# MB_RELAY.net
KiCad netlist of a schematic drawn in Altium Designer
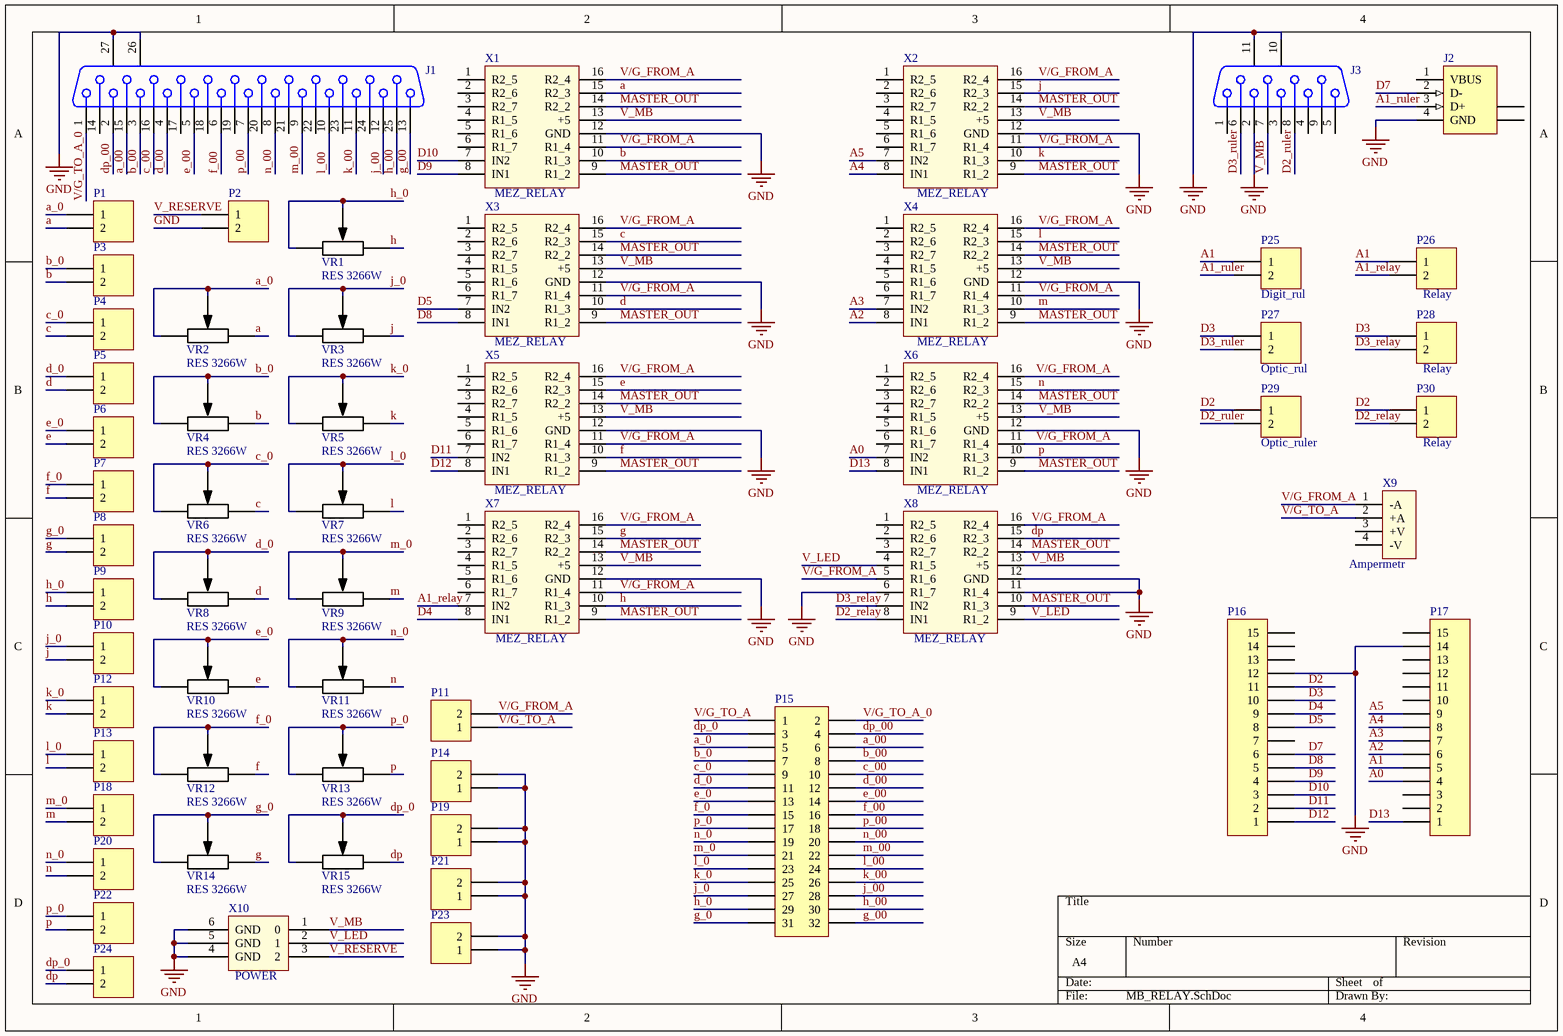
[diagram p0: MB_RELAY.SchDoc]

(export (version "E")
  (design (tool "Eeschema 10.0.6"))
  (components
    (comp (ref "J1")
      (value "D Connector 25")
      (footprint "DSUB1.385-2H25A")
      (description "Receptacle Assembly, 25 Position, Right Angle")
      (fields (field (name "PUBLISHER") "Altium Limited"))
      (libsource (lib "Miscellaneous Connectors") (part "D Connector 25"))
    )
    (comp (ref "J2")
      (value "1-353576-1")
      (footprint "353576")
      (description "USB 1.1, Right Angle, SMT, A Type, Receptacle, 4 Position, White")
      (fields (field (name "PUBLISHER") "Altium Limited"))
      (libsource (lib "AMP Serial Bus USB") (part "1-353576-1"))
    )
    (comp (ref "J3")
      (value "D Connector 9")
      (footprint "DSUB1.385-2H9")
      (description "Receptacle Assembly, 9 Position, Right Angle")
      (fields (field (name "PUBLISHER") "Altium Limited"))
      (libsource (lib "Miscellaneous Connectors") (part "D Connector 9"))
    )
    (comp (ref "P1")
      (value "Header 2")
      (footprint "HDR1X2")
      (description "Header, 2-Pin")
      (fields (field (name "PUBLISHER") "Altium Limited"))
      (libsource (lib "") (part "Header 2_1"))
    )
    (comp (ref "P2")
      (value "Header 2")
      (footprint "HDR1X2")
      (description "Header, 2-Pin")
      (fields (field (name "PUBLISHER") "Altium Limited"))
      (libsource (lib "") (part "Header 2_1"))
    )
    (comp (ref "P3")
      (value "Header 2")
      (footprint "HDR1X2")
      (description "Header, 2-Pin")
      (fields (field (name "PUBLISHER") "Altium Limited"))
      (libsource (lib "") (part "Header 2_1"))
    )
    (comp (ref "P4")
      (value "Header 2")
      (footprint "HDR1X2")
      (description "Header, 2-Pin")
      (fields (field (name "PUBLISHER") "Altium Limited"))
      (libsource (lib "") (part "Header 2_1"))
    )
    (comp (ref "P5")
      (value "Header 2")
      (footprint "HDR1X2")
      (description "Header, 2-Pin")
      (fields (field (name "PUBLISHER") "Altium Limited"))
      (libsource (lib "") (part "Header 2_1"))
    )
    (comp (ref "P6")
      (value "GND")
      (footprint "HDR1X2")
      (description "Header, 2-Pin")
      (fields (field (name "PUBLISHER") "Altium Limited"))
      (libsource (lib "") (part "Header 2_1"))
    )
    (comp (ref "P7")
      (value "GND")
      (footprint "HDR1X2")
      (description "Header, 2-Pin")
      (fields (field (name "PUBLISHER") "Altium Limited"))
      (libsource (lib "") (part "Header 2_1"))
    )
    (comp (ref "P8")
      (value "GND")
      (footprint "HDR1X2")
      (description "Header, 2-Pin")
      (fields (field (name "PUBLISHER") "Altium Limited"))
      (libsource (lib "") (part "Header 2_1"))
    )
    (comp (ref "P9")
      (value "GND")
      (footprint "HDR1X2")
      (description "Header, 2-Pin")
      (fields (field (name "PUBLISHER") "Altium Limited"))
      (libsource (lib "") (part "Header 2_1"))
    )
    (comp (ref "P10")
      (value "Header 2")
      (footprint "HDR1X2")
      (description "Header, 2-Pin")
      (fields (field (name "PUBLISHER") "Altium Limited"))
      (libsource (lib "") (part "Header 2_1"))
    )
    (comp (ref "P11")
      (value "Header 2")
      (footprint "HDR1X2")
      (description "Header, 2-Pin")
      (fields (field (name "PUBLISHER") "Altium Limited"))
      (libsource (lib "Miscellaneous Connectors") (part "Header 2"))
    )
    (comp (ref "P12")
      (value "Header 2")
      (footprint "HDR1X2")
      (description "Header, 2-Pin")
      (fields (field (name "PUBLISHER") "Altium Limited"))
      (libsource (lib "") (part "Header 2_1"))
    )
    (comp (ref "P13")
      (value "GND")
      (footprint "HDR1X2")
      (description "Header, 2-Pin")
      (fields (field (name "PUBLISHER") "Altium Limited"))
      (libsource (lib "") (part "Header 2_1"))
    )
    (comp (ref "P14")
      (value "GND")
      (footprint "HDR1X2")
      (description "Header, 2-Pin")
      (fields (field (name "PUBLISHER") "Altium Limited"))
      (libsource (lib "Miscellaneous Connectors") (part "Header 2"))
    )
    (comp (ref "P15")
      (value "Header 16X2")
      (footprint "HDR2X16")
      (description "Header, 16-Pin, Dual row")
      (fields (field (name "PUBLISHER") "Altium Limited"))
      (libsource (lib "Miscellaneous Connectors") (part "Header 16X2"))
    )
    (comp (ref "P16")
      (value "Header 15")
      (footprint "HDR1X15")
      (description "Header, 15-Pin")
      (fields (field (name "PUBLISHER") "Altium Limited"))
      (libsource (lib "") (part "Header 15_1"))
    )
    (comp (ref "P17")
      (value "Header 15")
      (footprint "HDR1X15")
      (description "Header, 15-Pin")
      (fields (field (name "PUBLISHER") "Altium Limited"))
      (libsource (lib "Miscellaneous Connectors") (part "Header 15"))
    )
    (comp (ref "P18")
      (value "GND")
      (footprint "HDR1X2")
      (description "Header, 2-Pin")
      (fields (field (name "PUBLISHER") "Altium Limited"))
      (libsource (lib "") (part "Header 2_1"))
    )
    (comp (ref "P19")
      (value "GND")
      (footprint "HDR1X2")
      (description "Header, 2-Pin")
      (fields (field (name "PUBLISHER") "Altium Limited"))
      (libsource (lib "Miscellaneous Connectors") (part "Header 2"))
    )
    (comp (ref "P20")
      (value "GND")
      (footprint "HDR1X2")
      (description "Header, 2-Pin")
      (fields (field (name "PUBLISHER") "Altium Limited"))
      (libsource (lib "") (part "Header 2_1"))
    )
    (comp (ref "P21")
      (value "GND")
      (footprint "HDR1X2")
      (description "Header, 2-Pin")
      (fields (field (name "PUBLISHER") "Altium Limited"))
      (libsource (lib "Miscellaneous Connectors") (part "Header 2"))
    )
    (comp (ref "P22")
      (value "GND")
      (footprint "HDR1X2")
      (description "Header, 2-Pin")
      (fields (field (name "PUBLISHER") "Altium Limited"))
      (libsource (lib "") (part "Header 2_1"))
    )
    (comp (ref "P23")
      (value "GND")
      (footprint "HDR1X2")
      (description "Header, 2-Pin")
      (fields (field (name "PUBLISHER") "Altium Limited"))
      (libsource (lib "Miscellaneous Connectors") (part "Header 2"))
    )
    (comp (ref "P24")
      (value "GND")
      (footprint "HDR1X2")
      (description "Header, 2-Pin")
      (fields (field (name "PUBLISHER") "Altium Limited"))
      (libsource (lib "") (part "Header 2_1"))
    )
    (comp (ref "P25")
      (value "Digit_rul")
      (footprint "HDR1X2")
      (description "Header, 2-Pin")
      (fields (field (name "PUBLISHER") "Altium Limited"))
      (libsource (lib "") (part "Header 2_1"))
    )
    (comp (ref "P26")
      (value "Relay")
      (footprint "HDR1X2")
      (description "Header, 2-Pin")
      (fields (field (name "PUBLISHER") "Altium Limited"))
      (libsource (lib "") (part "Header 2_1"))
    )
    (comp (ref "P27")
      (value "Optic_rul")
      (footprint "HDR1X2")
      (description "Header, 2-Pin")
      (fields (field (name "PUBLISHER") "Altium Limited"))
      (libsource (lib "") (part "Header 2_1"))
    )
    (comp (ref "P28")
      (value "Relay")
      (footprint "HDR1X2")
      (description "Header, 2-Pin")
      (fields (field (name "PUBLISHER") "Altium Limited"))
      (libsource (lib "") (part "Header 2_1"))
    )
    (comp (ref "P29")
      (value "Optic_ruler")
      (footprint "HDR1X2")
      (description "Header, 2-Pin")
      (fields (field (name "PUBLISHER") "Altium Limited"))
      (libsource (lib "") (part "Header 2_1"))
    )
    (comp (ref "P30")
      (value "Relay")
      (footprint "HDR1X2")
      (description "Header, 2-Pin")
      (fields (field (name "PUBLISHER") "Altium Limited"))
      (libsource (lib "") (part "Header 2_1"))
    )
    (comp (ref "VR1")
      (value "RES 3266W")
      (footprint "aab_Passive:RES 3266W")
      (libsource (lib "aab_Schlib") (part "RES 3266W"))
    )
    (comp (ref "VR2")
      (value "RES 3266W")
      (footprint "aab_Passive:RES 3266W")
      (libsource (lib "aab_Schlib") (part "RES 3266W"))
    )
    (comp (ref "VR3")
      (value "RES 3266W")
      (footprint "aab_Passive:RES 3266W")
      (libsource (lib "aab_Schlib") (part "RES 3266W"))
    )
    (comp (ref "VR4")
      (value "RES 3266W")
      (footprint "aab_Passive:RES 3266W")
      (libsource (lib "aab_Schlib") (part "RES 3266W"))
    )
    (comp (ref "VR5")
      (value "RES 3266W")
      (footprint "aab_Passive:RES 3266W")
      (libsource (lib "aab_Schlib") (part "RES 3266W"))
    )
    (comp (ref "VR6")
      (value "RES 3266W")
      (footprint "aab_Passive:RES 3266W")
      (libsource (lib "aab_Schlib") (part "RES 3266W"))
    )
    (comp (ref "VR7")
      (value "RES 3266W")
      (footprint "aab_Passive:RES 3266W")
      (libsource (lib "aab_Schlib") (part "RES 3266W"))
    )
    (comp (ref "VR8")
      (value "RES 3266W")
      (footprint "aab_Passive:RES 3266W")
      (libsource (lib "aab_Schlib") (part "RES 3266W"))
    )
    (comp (ref "VR9")
      (value "RES 3266W")
      (footprint "aab_Passive:RES 3266W")
      (libsource (lib "aab_Schlib") (part "RES 3266W"))
    )
    (comp (ref "VR10")
      (value "RES 3266W")
      (footprint "aab_Passive:RES 3266W")
      (libsource (lib "aab_Schlib") (part "RES 3266W"))
    )
    (comp (ref "VR11")
      (value "RES 3266W")
      (footprint "aab_Passive:RES 3266W")
      (libsource (lib "aab_Schlib") (part "RES 3266W"))
    )
    (comp (ref "VR12")
      (value "RES 3266W")
      (footprint "aab_Passive:RES 3266W")
      (libsource (lib "aab_Schlib") (part "RES 3266W"))
    )
    (comp (ref "VR13")
      (value "RES 3266W")
      (footprint "aab_Passive:RES 3266W")
      (libsource (lib "aab_Schlib") (part "RES 3266W"))
    )
    (comp (ref "VR14")
      (value "RES 3266W")
      (footprint "aab_Passive:RES 3266W")
      (libsource (lib "aab_Schlib") (part "RES 3266W"))
    )
    (comp (ref "VR15")
      (value "RES 3266W")
      (footprint "aab_Passive:RES 3266W")
      (libsource (lib "aab_Schlib") (part "RES 3266W"))
    )
    (comp (ref "X1")
      (value "MEZ_RELAY")
      (footprint "MEZ_RELAY")
      (libsource (lib "msp_SchLib") (part "MEZ_RELAY"))
    )
    (comp (ref "X2")
      (value "MEZ_RELAY")
      (footprint "MEZ_RELAY")
      (libsource (lib "msp_SchLib") (part "MEZ_RELAY"))
    )
    (comp (ref "X3")
      (value "MEZ_RELAY")
      (footprint "MEZ_RELAY")
      (libsource (lib "msp_SchLib") (part "MEZ_RELAY"))
    )
    (comp (ref "X4")
      (value "MEZ_RELAY")
      (footprint "MEZ_RELAY")
      (libsource (lib "msp_SchLib") (part "MEZ_RELAY"))
    )
    (comp (ref "X5")
      (value "MEZ_RELAY")
      (footprint "MEZ_RELAY")
      (libsource (lib "msp_SchLib") (part "MEZ_RELAY"))
    )
    (comp (ref "X6")
      (value "MEZ_RELAY")
      (footprint "MEZ_RELAY")
      (libsource (lib "msp_SchLib") (part "MEZ_RELAY"))
    )
    (comp (ref "X7")
      (value "MEZ_RELAY")
      (footprint "MEZ_RELAY")
      (libsource (lib "msp_SchLib") (part "MEZ_RELAY"))
    )
    (comp (ref "X8")
      (value "MEZ_RELAY")
      (footprint "MEZ_RELAY")
      (libsource (lib "msp_SchLib") (part "MEZ_RELAY"))
    )
    (comp (ref "X9")
      (value "Ampermetr")
      (footprint "vpl_Passive:AMP_VOLTMETER")
      (libsource (lib "msp_SchLib") (part "AMP_VOLTMETR"))
    )
    (comp (ref "X10")
      (value "POWER")
      (footprint "vpl_Passive:POWER")
      (libsource (lib "msp_SchLib") (part "POWER"))
    )
  )
  (nets
    (net (code "1") (name "/A0") (class "Default")
      (node (ref "P17") (pin "4") (pinfunction "4_4") (pintype "passive"))
      (node (ref "X6") (pin "7") (pinfunction "IN2_7") (pintype "passive"))
    )
    (net (code "2") (name "/A1") (class "Default")
      (node (ref "P17") (pin "5") (pinfunction "5_5") (pintype "passive"))
      (node (ref "P25") (pin "1") (pinfunction "1_1") (pintype "passive"))
      (node (ref "P26") (pin "1") (pinfunction "1_1") (pintype "passive"))
    )
    (net (code "3") (name "/A1_relay") (class "Default")
      (node (ref "P26") (pin "2") (pinfunction "2_2") (pintype "passive"))
      (node (ref "X7") (pin "7") (pinfunction "IN2_7") (pintype "passive"))
    )
    (net (code "4") (name "/A1_ruler") (class "Default")
      (node (ref "J2") (pin "3") (pinfunction "D+_3") (pintype "input"))
      (node (ref "P25") (pin "2") (pinfunction "2_2") (pintype "passive"))
    )
    (net (code "5") (name "/A2") (class "Default")
      (node (ref "P17") (pin "6") (pinfunction "6_6") (pintype "passive"))
      (node (ref "X4") (pin "8") (pinfunction "IN1_8") (pintype "passive"))
    )
    (net (code "6") (name "/A3") (class "Default")
      (node (ref "P17") (pin "7") (pinfunction "7_7") (pintype "passive"))
      (node (ref "X4") (pin "7") (pinfunction "IN2_7") (pintype "passive"))
    )
    (net (code "7") (name "/A4") (class "Default")
      (node (ref "P17") (pin "8") (pinfunction "8_8") (pintype "passive"))
      (node (ref "X2") (pin "8") (pinfunction "IN1_8") (pintype "passive"))
    )
    (net (code "8") (name "/A5") (class "Default")
      (node (ref "P17") (pin "9") (pinfunction "9_9") (pintype "passive"))
      (node (ref "X2") (pin "7") (pinfunction "IN2_7") (pintype "passive"))
    )
    (net (code "9") (name "/D2") (class "Default")
      (node (ref "P16") (pin "11") (pinfunction "11_11") (pintype "passive"))
      (node (ref "P29") (pin "1") (pinfunction "1_1") (pintype "passive"))
      (node (ref "P30") (pin "1") (pinfunction "1_1") (pintype "passive"))
    )
    (net (code "10") (name "/D2_relay") (class "Default")
      (node (ref "P30") (pin "2") (pinfunction "2_2") (pintype "passive"))
      (node (ref "X8") (pin "8") (pinfunction "IN1_8") (pintype "passive"))
    )
    (net (code "11") (name "/D2_ruler") (class "Default")
      (node (ref "J3") (pin "8") (pinfunction "8_8") (pintype "passive"))
      (node (ref "P29") (pin "2") (pinfunction "2_2") (pintype "passive"))
    )
    (net (code "12") (name "/D3") (class "Default")
      (node (ref "P16") (pin "10") (pinfunction "10_10") (pintype "passive"))
      (node (ref "P27") (pin "1") (pinfunction "1_1") (pintype "passive"))
      (node (ref "P28") (pin "1") (pinfunction "1_1") (pintype "passive"))
    )
    (net (code "13") (name "/D3_relay") (class "Default")
      (node (ref "P28") (pin "2") (pinfunction "2_2") (pintype "passive"))
      (node (ref "X8") (pin "7") (pinfunction "IN2_7") (pintype "passive"))
    )
    (net (code "14") (name "/D3_ruler") (class "Default")
      (node (ref "J3") (pin "6") (pinfunction "6_6") (pintype "passive"))
      (node (ref "P27") (pin "2") (pinfunction "2_2") (pintype "passive"))
    )
    (net (code "15") (name "/D4") (class "Default")
      (node (ref "P16") (pin "9") (pinfunction "9_9") (pintype "passive"))
      (node (ref "X7") (pin "8") (pinfunction "IN1_8") (pintype "passive"))
    )
    (net (code "16") (name "/D5") (class "Default")
      (node (ref "P16") (pin "8") (pinfunction "8_8") (pintype "passive"))
      (node (ref "X3") (pin "7") (pinfunction "IN2_7") (pintype "passive"))
    )
    (net (code "17") (name "/D7") (class "Default")
      (node (ref "J2") (pin "2") (pinfunction "D-_2") (pintype "input"))
      (node (ref "P16") (pin "6") (pinfunction "6_6") (pintype "passive"))
    )
    (net (code "18") (name "/D8") (class "Default")
      (node (ref "P16") (pin "5") (pinfunction "5_5") (pintype "passive"))
      (node (ref "X3") (pin "8") (pinfunction "IN1_8") (pintype "passive"))
    )
    (net (code "19") (name "/D9") (class "Default")
      (node (ref "P16") (pin "4") (pinfunction "4_4") (pintype "passive"))
      (node (ref "X1") (pin "8") (pinfunction "IN1_8") (pintype "passive"))
    )
    (net (code "20") (name "/D10") (class "Default")
      (node (ref "P16") (pin "3") (pinfunction "3_3") (pintype "passive"))
      (node (ref "X1") (pin "7") (pinfunction "IN2_7") (pintype "passive"))
    )
    (net (code "21") (name "/D11") (class "Default")
      (node (ref "P16") (pin "2") (pinfunction "2_2") (pintype "passive"))
      (node (ref "X5") (pin "7") (pinfunction "IN2_7") (pintype "passive"))
    )
    (net (code "22") (name "/D12") (class "Default")
      (node (ref "P16") (pin "1") (pinfunction "1_1") (pintype "passive"))
      (node (ref "X5") (pin "8") (pinfunction "IN1_8") (pintype "passive"))
    )
    (net (code "23") (name "/D13") (class "Default")
      (node (ref "P17") (pin "1") (pinfunction "1_1") (pintype "passive"))
      (node (ref "X6") (pin "8") (pinfunction "IN1_8") (pintype "passive"))
    )
    (net (code "24") (name "/MASTER_OUT") (class "Default")
      (node (ref "X1") (pin "14") (pinfunction "R2_2_14") (pintype "passive"))
      (node (ref "X1") (pin "9") (pinfunction "R1_2_9") (pintype "passive"))
      (node (ref "X2") (pin "14") (pinfunction "R2_2_14") (pintype "passive"))
      (node (ref "X2") (pin "9") (pinfunction "R1_2_9") (pintype "passive"))
      (node (ref "X3") (pin "14") (pinfunction "R2_2_14") (pintype "passive"))
      (node (ref "X3") (pin "9") (pinfunction "R1_2_9") (pintype "passive"))
      (node (ref "X4") (pin "14") (pinfunction "R2_2_14") (pintype "passive"))
      (node (ref "X4") (pin "9") (pinfunction "R1_2_9") (pintype "passive"))
      (node (ref "X5") (pin "14") (pinfunction "R2_2_14") (pintype "passive"))
      (node (ref "X5") (pin "9") (pinfunction "R1_2_9") (pintype "passive"))
      (node (ref "X6") (pin "14") (pinfunction "R2_2_14") (pintype "passive"))
      (node (ref "X6") (pin "9") (pinfunction "R1_2_9") (pintype "passive"))
      (node (ref "X7") (pin "14") (pinfunction "R2_2_14") (pintype "passive"))
      (node (ref "X7") (pin "9") (pinfunction "R1_2_9") (pintype "passive"))
      (node (ref "X8") (pin "10") (pinfunction "R1_3_10") (pintype "passive"))
      (node (ref "X8") (pin "14") (pinfunction "R2_2_14") (pintype "passive"))
    )
    (net (code "25") (name "/V_LED") (class "Default")
      (node (ref "X10") (pin "2") (pinfunction "1_2") (pintype "passive"))
      (node (ref "X8") (pin "4") (pinfunction "R1_5_4") (pintype "passive"))
      (node (ref "X8") (pin "9") (pinfunction "R1_2_9") (pintype "passive"))
    )
    (net (code "26") (name "/V_MB") (class "Default")
      (node (ref "J3") (pin "7") (pinfunction "7_7") (pintype "passive"))
      (node (ref "X1") (pin "13") (pinfunction "+5_13") (pintype "passive"))
      (node (ref "X10") (pin "1") (pinfunction "0_1") (pintype "passive"))
      (node (ref "X2") (pin "13") (pinfunction "+5_13") (pintype "passive"))
      (node (ref "X3") (pin "13") (pinfunction "+5_13") (pintype "passive"))
      (node (ref "X4") (pin "13") (pinfunction "+5_13") (pintype "passive"))
      (node (ref "X5") (pin "13") (pinfunction "+5_13") (pintype "passive"))
      (node (ref "X6") (pin "13") (pinfunction "+5_13") (pintype "passive"))
      (node (ref "X7") (pin "13") (pinfunction "+5_13") (pintype "passive"))
      (node (ref "X8") (pin "13") (pinfunction "+5_13") (pintype "passive"))
    )
    (net (code "27") (name "/V_RESERVE") (class "Default")
      (node (ref "P2") (pin "1") (pinfunction "1_1") (pintype "passive"))
      (node (ref "X10") (pin "3") (pinfunction "2_3") (pintype "passive"))
    )
    (net (code "28") (name "/V{slash}G_FROM_A") (class "Default")
      (node (ref "P11") (pin "2") (pinfunction "2_2") (pintype "passive"))
      (node (ref "X1") (pin "11") (pinfunction "R1_4_11") (pintype "passive"))
      (node (ref "X1") (pin "16") (pinfunction "R2_4_16") (pintype "passive"))
      (node (ref "X2") (pin "11") (pinfunction "R1_4_11") (pintype "passive"))
      (node (ref "X2") (pin "16") (pinfunction "R2_4_16") (pintype "passive"))
      (node (ref "X3") (pin "11") (pinfunction "R1_4_11") (pintype "passive"))
      (node (ref "X3") (pin "16") (pinfunction "R2_4_16") (pintype "passive"))
      (node (ref "X4") (pin "11") (pinfunction "R1_4_11") (pintype "passive"))
      (node (ref "X4") (pin "16") (pinfunction "R2_4_16") (pintype "passive"))
      (node (ref "X5") (pin "11") (pinfunction "R1_4_11") (pintype "passive"))
      (node (ref "X5") (pin "16") (pinfunction "R2_4_16") (pintype "passive"))
      (node (ref "X6") (pin "11") (pinfunction "R1_4_11") (pintype "passive"))
      (node (ref "X6") (pin "16") (pinfunction "R2_4_16") (pintype "passive"))
      (node (ref "X7") (pin "11") (pinfunction "R1_4_11") (pintype "passive"))
      (node (ref "X7") (pin "16") (pinfunction "R2_4_16") (pintype "passive"))
      (node (ref "X8") (pin "16") (pinfunction "R2_4_16") (pintype "passive"))
      (node (ref "X8") (pin "5") (pinfunction "R1_6_5") (pintype "passive"))
      (node (ref "X9") (pin "1") (pinfunction "-A_1") (pintype "passive"))
    )
    (net (code "29") (name "/V{slash}G_TO_A") (class "Default")
      (node (ref "P11") (pin "1") (pinfunction "1_1") (pintype "passive"))
      (node (ref "P15") (pin "1") (pinfunction "1_1") (pintype "passive"))
      (node (ref "X9") (pin "2") (pinfunction "+A_2") (pintype "passive"))
    )
    (net (code "30") (name "/V{slash}G_TO_A_0") (class "Default")
      (node (ref "J1") (pin "1") (pinfunction "1_1") (pintype "passive"))
      (node (ref "P15") (pin "2") (pinfunction "2_2") (pintype "passive"))
    )
    (net (code "31") (name "/a") (class "Default")
      (node (ref "P1") (pin "2") (pinfunction "2_2") (pintype "passive"))
      (node (ref "VR2") (pin "3") (pinfunction "3_3") (pintype "passive"))
      (node (ref "X1") (pin "15") (pinfunction "R2_3_15") (pintype "passive"))
    )
    (net (code "32") (name "/a_0") (class "Default")
      (node (ref "P1") (pin "1") (pinfunction "1_1") (pintype "passive"))
      (node (ref "P15") (pin "5") (pinfunction "5_5") (pintype "passive"))
      (node (ref "VR2") (pin "1") (pinfunction "1_1") (pintype "passive"))
      (node (ref "VR2") (pin "2") (pinfunction "2_2") (pintype "passive"))
    )
    (net (code "33") (name "/a_00") (class "Default")
      (node (ref "J1") (pin "15") (pinfunction "15_15") (pintype "passive"))
      (node (ref "P15") (pin "6") (pinfunction "6_6") (pintype "passive"))
    )
    (net (code "34") (name "/b") (class "Default")
      (node (ref "P3") (pin "2") (pinfunction "2_2") (pintype "passive"))
      (node (ref "VR4") (pin "3") (pinfunction "3_3") (pintype "passive"))
      (node (ref "X1") (pin "10") (pinfunction "R1_3_10") (pintype "passive"))
    )
    (net (code "35") (name "/b_0") (class "Default")
      (node (ref "P15") (pin "7") (pinfunction "7_7") (pintype "passive"))
      (node (ref "P3") (pin "1") (pinfunction "1_1") (pintype "passive"))
      (node (ref "VR4") (pin "1") (pinfunction "1_1") (pintype "passive"))
      (node (ref "VR4") (pin "2") (pinfunction "2_2") (pintype "passive"))
    )
    (net (code "36") (name "/b_00") (class "Default")
      (node (ref "J1") (pin "3") (pinfunction "3_3") (pintype "passive"))
      (node (ref "P15") (pin "8") (pinfunction "8_8") (pintype "passive"))
    )
    (net (code "37") (name "/c") (class "Default")
      (node (ref "P4") (pin "2") (pinfunction "2_2") (pintype "passive"))
      (node (ref "VR6") (pin "3") (pinfunction "3_3") (pintype "passive"))
      (node (ref "X3") (pin "15") (pinfunction "R2_3_15") (pintype "passive"))
    )
    (net (code "38") (name "/c_0") (class "Default")
      (node (ref "P15") (pin "9") (pinfunction "9_9") (pintype "passive"))
      (node (ref "P4") (pin "1") (pinfunction "1_1") (pintype "passive"))
      (node (ref "VR6") (pin "1") (pinfunction "1_1") (pintype "passive"))
      (node (ref "VR6") (pin "2") (pinfunction "2_2") (pintype "passive"))
    )
    (net (code "39") (name "/c_00") (class "Default")
      (node (ref "J1") (pin "16") (pinfunction "16_16") (pintype "passive"))
      (node (ref "P15") (pin "10") (pinfunction "10_10") (pintype "passive"))
    )
    (net (code "40") (name "/d") (class "Default")
      (node (ref "P5") (pin "2") (pinfunction "2_2") (pintype "passive"))
      (node (ref "VR8") (pin "3") (pinfunction "3_3") (pintype "passive"))
      (node (ref "X3") (pin "10") (pinfunction "R1_3_10") (pintype "passive"))
    )
    (net (code "41") (name "/d_00") (class "Default")
      (node (ref "J1") (pin "4") (pinfunction "4_4") (pintype "passive"))
      (node (ref "P15") (pin "12") (pinfunction "12_12") (pintype "passive"))
    )
    (net (code "42") (name "/d_0") (class "Default")
      (node (ref "P15") (pin "11") (pinfunction "11_11") (pintype "passive"))
      (node (ref "P5") (pin "1") (pinfunction "1_1") (pintype "passive"))
      (node (ref "VR8") (pin "1") (pinfunction "1_1") (pintype "passive"))
      (node (ref "VR8") (pin "2") (pinfunction "2_2") (pintype "passive"))
    )
    (net (code "43") (name "/dp") (class "Default")
      (node (ref "P24") (pin "2") (pinfunction "2_2") (pintype "passive"))
      (node (ref "VR15") (pin "3") (pinfunction "3_3") (pintype "passive"))
      (node (ref "X8") (pin "15") (pinfunction "R2_3_15") (pintype "passive"))
    )
    (net (code "44") (name "/dp_0") (class "Default")
      (node (ref "P15") (pin "3") (pinfunction "3_3") (pintype "passive"))
      (node (ref "P24") (pin "1") (pinfunction "1_1") (pintype "passive"))
      (node (ref "VR15") (pin "1") (pinfunction "1_1") (pintype "passive"))
      (node (ref "VR15") (pin "2") (pinfunction "2_2") (pintype "passive"))
    )
    (net (code "45") (name "/dp_00") (class "Default")
      (node (ref "J1") (pin "2") (pinfunction "2_2") (pintype "passive"))
      (node (ref "P15") (pin "4") (pinfunction "4_4") (pintype "passive"))
    )
    (net (code "46") (name "/e") (class "Default")
      (node (ref "P6") (pin "2") (pinfunction "2_2") (pintype "passive"))
      (node (ref "VR10") (pin "3") (pinfunction "3_3") (pintype "passive"))
      (node (ref "X5") (pin "15") (pinfunction "R2_3_15") (pintype "passive"))
    )
    (net (code "47") (name "/e_0") (class "Default")
      (node (ref "P15") (pin "13") (pinfunction "13_13") (pintype "passive"))
      (node (ref "P6") (pin "1") (pinfunction "1_1") (pintype "passive"))
      (node (ref "VR10") (pin "1") (pinfunction "1_1") (pintype "passive"))
      (node (ref "VR10") (pin "2") (pinfunction "2_2") (pintype "passive"))
    )
    (net (code "48") (name "/e_00") (class "Default")
      (node (ref "J1") (pin "5") (pinfunction "5_5") (pintype "passive"))
      (node (ref "P15") (pin "14") (pinfunction "14_14") (pintype "passive"))
    )
    (net (code "49") (name "/f") (class "Default")
      (node (ref "P7") (pin "2") (pinfunction "2_2") (pintype "passive"))
      (node (ref "VR12") (pin "3") (pinfunction "3_3") (pintype "passive"))
      (node (ref "X5") (pin "10") (pinfunction "R1_3_10") (pintype "passive"))
    )
    (net (code "50") (name "/f_0") (class "Default")
      (node (ref "P15") (pin "15") (pinfunction "15_15") (pintype "passive"))
      (node (ref "P7") (pin "1") (pinfunction "1_1") (pintype "passive"))
      (node (ref "VR12") (pin "1") (pinfunction "1_1") (pintype "passive"))
      (node (ref "VR12") (pin "2") (pinfunction "2_2") (pintype "passive"))
    )
    (net (code "51") (name "/f_00") (class "Default")
      (node (ref "J1") (pin "6") (pinfunction "6_6") (pintype "passive"))
      (node (ref "P15") (pin "16") (pinfunction "16_16") (pintype "passive"))
    )
    (net (code "52") (name "/g") (class "Default")
      (node (ref "P8") (pin "2") (pinfunction "2_2") (pintype "passive"))
      (node (ref "VR14") (pin "3") (pinfunction "3_3") (pintype "passive"))
      (node (ref "X7") (pin "15") (pinfunction "R2_3_15") (pintype "passive"))
    )
    (net (code "53") (name "/g_0") (class "Default")
      (node (ref "P15") (pin "31") (pinfunction "31_31") (pintype "passive"))
      (node (ref "P8") (pin "1") (pinfunction "1_1") (pintype "passive"))
      (node (ref "VR14") (pin "1") (pinfunction "1_1") (pintype "passive"))
      (node (ref "VR14") (pin "2") (pinfunction "2_2") (pintype "passive"))
    )
    (net (code "54") (name "/g_00") (class "Default")
      (node (ref "J1") (pin "13") (pinfunction "13_13") (pintype "passive"))
      (node (ref "P15") (pin "32") (pinfunction "32_32") (pintype "passive"))
    )
    (net (code "55") (name "/h") (class "Default")
      (node (ref "P9") (pin "2") (pinfunction "2_2") (pintype "passive"))
      (node (ref "VR1") (pin "3") (pinfunction "3_3") (pintype "passive"))
      (node (ref "X7") (pin "10") (pinfunction "R1_3_10") (pintype "passive"))
    )
    (net (code "56") (name "/h_00") (class "Default")
      (node (ref "J1") (pin "25") (pinfunction "25_25") (pintype "passive"))
      (node (ref "P15") (pin "30") (pinfunction "30_30") (pintype "passive"))
    )
    (net (code "57") (name "/h_0") (class "Default")
      (node (ref "P15") (pin "29") (pinfunction "29_29") (pintype "passive"))
      (node (ref "P9") (pin "1") (pinfunction "1_1") (pintype "passive"))
      (node (ref "VR1") (pin "1") (pinfunction "1_1") (pintype "passive"))
      (node (ref "VR1") (pin "2") (pinfunction "2_2") (pintype "passive"))
    )
    (net (code "58") (name "/j") (class "Default")
      (node (ref "P10") (pin "2") (pinfunction "2_2") (pintype "passive"))
      (node (ref "VR3") (pin "3") (pinfunction "3_3") (pintype "passive"))
      (node (ref "X2") (pin "15") (pinfunction "R2_3_15") (pintype "passive"))
    )
    (net (code "59") (name "/j_0") (class "Default")
      (node (ref "P10") (pin "1") (pinfunction "1_1") (pintype "passive"))
      (node (ref "P15") (pin "27") (pinfunction "27_27") (pintype "passive"))
      (node (ref "VR3") (pin "1") (pinfunction "1_1") (pintype "passive"))
      (node (ref "VR3") (pin "2") (pinfunction "2_2") (pintype "passive"))
    )
    (net (code "60") (name "/j_00") (class "Default")
      (node (ref "J1") (pin "12") (pinfunction "12_12") (pintype "passive"))
      (node (ref "P15") (pin "28") (pinfunction "28_28") (pintype "passive"))
    )
    (net (code "61") (name "/k") (class "Default")
      (node (ref "P12") (pin "2") (pinfunction "2_2") (pintype "passive"))
      (node (ref "VR5") (pin "3") (pinfunction "3_3") (pintype "passive"))
      (node (ref "X2") (pin "10") (pinfunction "R1_3_10") (pintype "passive"))
    )
    (net (code "62") (name "/k_0") (class "Default")
      (node (ref "P12") (pin "1") (pinfunction "1_1") (pintype "passive"))
      (node (ref "P15") (pin "25") (pinfunction "25_25") (pintype "passive"))
      (node (ref "VR5") (pin "1") (pinfunction "1_1") (pintype "passive"))
      (node (ref "VR5") (pin "2") (pinfunction "2_2") (pintype "passive"))
    )
    (net (code "63") (name "/k_00") (class "Default")
      (node (ref "J1") (pin "11") (pinfunction "11_11") (pintype "passive"))
      (node (ref "P15") (pin "26") (pinfunction "26_26") (pintype "passive"))
    )
    (net (code "64") (name "/l") (class "Default")
      (node (ref "P13") (pin "2") (pinfunction "2_2") (pintype "passive"))
      (node (ref "VR7") (pin "3") (pinfunction "3_3") (pintype "passive"))
      (node (ref "X4") (pin "15") (pinfunction "R2_3_15") (pintype "passive"))
    )
    (net (code "65") (name "/l_0") (class "Default")
      (node (ref "P13") (pin "1") (pinfunction "1_1") (pintype "passive"))
      (node (ref "P15") (pin "23") (pinfunction "23_23") (pintype "passive"))
      (node (ref "VR7") (pin "1") (pinfunction "1_1") (pintype "passive"))
      (node (ref "VR7") (pin "2") (pinfunction "2_2") (pintype "passive"))
    )
    (net (code "66") (name "/l_00") (class "Default")
      (node (ref "J1") (pin "10") (pinfunction "10_10") (pintype "passive"))
      (node (ref "P15") (pin "24") (pinfunction "24_24") (pintype "passive"))
    )
    (net (code "67") (name "/m") (class "Default")
      (node (ref "P18") (pin "2") (pinfunction "2_2") (pintype "passive"))
      (node (ref "VR9") (pin "3") (pinfunction "3_3") (pintype "passive"))
      (node (ref "X4") (pin "10") (pinfunction "R1_3_10") (pintype "passive"))
    )
    (net (code "68") (name "/m_0") (class "Default")
      (node (ref "P15") (pin "21") (pinfunction "21_21") (pintype "passive"))
      (node (ref "P18") (pin "1") (pinfunction "1_1") (pintype "passive"))
      (node (ref "VR9") (pin "1") (pinfunction "1_1") (pintype "passive"))
      (node (ref "VR9") (pin "2") (pinfunction "2_2") (pintype "passive"))
    )
    (net (code "69") (name "/m_00") (class "Default")
      (node (ref "J1") (pin "9") (pinfunction "9_9") (pintype "passive"))
      (node (ref "P15") (pin "22") (pinfunction "22_22") (pintype "passive"))
    )
    (net (code "70") (name "/n") (class "Default")
      (node (ref "P20") (pin "2") (pinfunction "2_2") (pintype "passive"))
      (node (ref "VR11") (pin "3") (pinfunction "3_3") (pintype "passive"))
      (node (ref "X6") (pin "15") (pinfunction "R2_3_15") (pintype "passive"))
    )
    (net (code "71") (name "/n_0") (class "Default")
      (node (ref "P15") (pin "19") (pinfunction "19_19") (pintype "passive"))
      (node (ref "P20") (pin "1") (pinfunction "1_1") (pintype "passive"))
      (node (ref "VR11") (pin "1") (pinfunction "1_1") (pintype "passive"))
      (node (ref "VR11") (pin "2") (pinfunction "2_2") (pintype "passive"))
    )
    (net (code "72") (name "/n_00") (class "Default")
      (node (ref "J1") (pin "8") (pinfunction "8_8") (pintype "passive"))
      (node (ref "P15") (pin "20") (pinfunction "20_20") (pintype "passive"))
    )
    (net (code "73") (name "/p") (class "Default")
      (node (ref "P22") (pin "2") (pinfunction "2_2") (pintype "passive"))
      (node (ref "VR13") (pin "3") (pinfunction "3_3") (pintype "passive"))
      (node (ref "X6") (pin "10") (pinfunction "R1_3_10") (pintype "passive"))
    )
    (net (code "74") (name "/p_0") (class "Default")
      (node (ref "P15") (pin "17") (pinfunction "17_17") (pintype "passive"))
      (node (ref "P22") (pin "1") (pinfunction "1_1") (pintype "passive"))
      (node (ref "VR13") (pin "1") (pinfunction "1_1") (pintype "passive"))
      (node (ref "VR13") (pin "2") (pinfunction "2_2") (pintype "passive"))
    )
    (net (code "75") (name "/p_00") (class "Default")
      (node (ref "J1") (pin "7") (pinfunction "7_7") (pintype "passive"))
      (node (ref "P15") (pin "18") (pinfunction "18_18") (pintype "passive"))
    )
    (net (code "76") (name "GND") (class "Default")
      (node (ref "J1") (pin "26") (pinfunction "MH1_26") (pintype "passive"))
      (node (ref "J1") (pin "27") (pinfunction "MH2_27") (pintype "passive"))
      (node (ref "J2") (pin "4") (pinfunction "GND_4") (pintype "power_in"))
      (node (ref "J3") (pin "10") (pinfunction "MH1_10") (pintype "passive"))
      (node (ref "J3") (pin "11") (pinfunction "MH2_11") (pintype "passive"))
      (node (ref "J3") (pin "2") (pinfunction "2_2") (pintype "passive"))
      (node (ref "P14") (pin "1") (pinfunction "1_1") (pintype "passive"))
      (node (ref "P14") (pin "2") (pinfunction "2_2") (pintype "passive"))
      (node (ref "P16") (pin "12") (pinfunction "12_12") (pintype "passive"))
      (node (ref "P17") (pin "14") (pinfunction "14_14") (pintype "passive"))
      (node (ref "P19") (pin "1") (pinfunction "1_1") (pintype "passive"))
      (node (ref "P19") (pin "2") (pinfunction "2_2") (pintype "passive"))
      (node (ref "P2") (pin "2") (pinfunction "2_2") (pintype "passive"))
      (node (ref "P21") (pin "1") (pinfunction "1_1") (pintype "passive"))
      (node (ref "P21") (pin "2") (pinfunction "2_2") (pintype "passive"))
      (node (ref "P23") (pin "1") (pinfunction "1_1") (pintype "passive"))
      (node (ref "P23") (pin "2") (pinfunction "2_2") (pintype "passive"))
      (node (ref "X1") (pin "12") (pinfunction "GND_12") (pintype "passive"))
      (node (ref "X10") (pin "4") (pinfunction "GND_4") (pintype "passive"))
      (node (ref "X10") (pin "5") (pinfunction "GND_5") (pintype "passive"))
      (node (ref "X10") (pin "6") (pinfunction "GND_6") (pintype "passive"))
      (node (ref "X2") (pin "12") (pinfunction "GND_12") (pintype "passive"))
      (node (ref "X3") (pin "12") (pinfunction "GND_12") (pintype "passive"))
      (node (ref "X4") (pin "12") (pinfunction "GND_12") (pintype "passive"))
      (node (ref "X5") (pin "12") (pinfunction "GND_12") (pintype "passive"))
      (node (ref "X6") (pin "12") (pinfunction "GND_12") (pintype "passive"))
      (node (ref "X7") (pin "12") (pinfunction "GND_12") (pintype "passive"))
      (node (ref "X8") (pin "11") (pinfunction "R1_4_11") (pintype "passive"))
      (node (ref "X8") (pin "12") (pinfunction "GND_12") (pintype "passive"))
      (node (ref "X8") (pin "6") (pinfunction "R1_7_6") (pintype "passive"))
    )
    (net (code "77") (name "unconnected-(J1-Pad14)") (class "Default")
      (node (ref "J1") (pin "14") (pinfunction "14_14") (pintype "passive"))
    )
    (net (code "78") (name "unconnected-(J1-Pad17)") (class "Default")
      (node (ref "J1") (pin "17") (pinfunction "17_17") (pintype "passive"))
    )
    (net (code "79") (name "unconnected-(J1-Pad18)") (class "Default")
      (node (ref "J1") (pin "18") (pinfunction "18_18") (pintype "passive"))
    )
    (net (code "80") (name "unconnected-(J1-Pad19)") (class "Default")
      (node (ref "J1") (pin "19") (pinfunction "19_19") (pintype "passive"))
    )
    (net (code "81") (name "unconnected-(J1-Pad20)") (class "Default")
      (node (ref "J1") (pin "20") (pinfunction "20_20") (pintype "passive"))
    )
    (net (code "82") (name "unconnected-(J1-Pad21)") (class "Default")
      (node (ref "J1") (pin "21") (pinfunction "21_21") (pintype "passive"))
    )
    (net (code "83") (name "unconnected-(J1-Pad22)") (class "Default")
      (node (ref "J1") (pin "22") (pinfunction "22_22") (pintype "passive"))
    )
    (net (code "84") (name "unconnected-(J1-Pad23)") (class "Default")
      (node (ref "J1") (pin "23") (pinfunction "23_23") (pintype "passive"))
    )
    (net (code "85") (name "unconnected-(J1-Pad24)") (class "Default")
      (node (ref "J1") (pin "24") (pinfunction "24_24") (pintype "passive"))
    )
    (net (code "86") (name "unconnected-(J2-SHLD-Pad5)") (class "Default")
      (node (ref "J2") (pin "5") (pinfunction "SHLD_5") (pintype "passive"))
    )
    (net (code "87") (name "unconnected-(J2-SHLD-Pad6)") (class "Default")
      (node (ref "J2") (pin "6") (pinfunction "SHLD_6") (pintype "passive"))
    )
    (net (code "88") (name "unconnected-(J2-VBUS-Pad1)") (class "Default")
      (node (ref "J2") (pin "1") (pinfunction "VBUS_1") (pintype "power_in"))
    )
    (net (code "89") (name "unconnected-(J3-Pad1)") (class "Default")
      (node (ref "J3") (pin "1") (pinfunction "1_1") (pintype "passive"))
    )
    (net (code "90") (name "unconnected-(J3-Pad3)") (class "Default")
      (node (ref "J3") (pin "3") (pinfunction "3_3") (pintype "passive"))
    )
    (net (code "91") (name "unconnected-(J3-Pad4)") (class "Default")
      (node (ref "J3") (pin "4") (pinfunction "4_4") (pintype "passive"))
    )
    (net (code "92") (name "unconnected-(J3-Pad5)") (class "Default")
      (node (ref "J3") (pin "5") (pinfunction "5_5") (pintype "passive"))
    )
    (net (code "93") (name "unconnected-(J3-Pad9)") (class "Default")
      (node (ref "J3") (pin "9") (pinfunction "9_9") (pintype "passive"))
    )
    (net (code "94") (name "unconnected-(P16-Pad7)") (class "Default")
      (node (ref "P16") (pin "7") (pinfunction "7_7") (pintype "passive"))
    )
    (net (code "95") (name "unconnected-(P16-Pad13)") (class "Default")
      (node (ref "P16") (pin "13") (pinfunction "13_13") (pintype "passive"))
    )
    (net (code "96") (name "unconnected-(P16-Pad14)") (class "Default")
      (node (ref "P16") (pin "14") (pinfunction "14_14") (pintype "passive"))
    )
    (net (code "97") (name "unconnected-(P16-Pad15)") (class "Default")
      (node (ref "P16") (pin "15") (pinfunction "15_15") (pintype "passive"))
    )
    (net (code "98") (name "unconnected-(P17-Pad2)") (class "Default")
      (node (ref "P17") (pin "2") (pinfunction "2_2") (pintype "passive"))
    )
    (net (code "99") (name "unconnected-(P17-Pad3)") (class "Default")
      (node (ref "P17") (pin "3") (pinfunction "3_3") (pintype "passive"))
    )
    (net (code "100") (name "unconnected-(P17-Pad10)") (class "Default")
      (node (ref "P17") (pin "10") (pinfunction "10_10") (pintype "passive"))
    )
    (net (code "101") (name "unconnected-(P17-Pad11)") (class "Default")
      (node (ref "P17") (pin "11") (pinfunction "11_11") (pintype "passive"))
    )
    (net (code "102") (name "unconnected-(P17-Pad12)") (class "Default")
      (node (ref "P17") (pin "12") (pinfunction "12_12") (pintype "passive"))
    )
    (net (code "103") (name "unconnected-(P17-Pad13)") (class "Default")
      (node (ref "P17") (pin "13") (pinfunction "13_13") (pintype "passive"))
    )
    (net (code "104") (name "unconnected-(P17-Pad15)") (class "Default")
      (node (ref "P17") (pin "15") (pinfunction "15_15") (pintype "passive"))
    )
    (net (code "105") (name "unconnected-(X1-R1_5-Pad4)") (class "Default")
      (node (ref "X1") (pin "4") (pinfunction "R1_5_4") (pintype "passive"))
    )
    (net (code "106") (name "unconnected-(X1-R1_6-Pad5)") (class "Default")
      (node (ref "X1") (pin "5") (pinfunction "R1_6_5") (pintype "passive"))
    )
    (net (code "107") (name "unconnected-(X1-R1_7-Pad6)") (class "Default")
      (node (ref "X1") (pin "6") (pinfunction "R1_7_6") (pintype "passive"))
    )
    (net (code "108") (name "unconnected-(X1-R2_5-Pad1)") (class "Default")
      (node (ref "X1") (pin "1") (pinfunction "R2_5_1") (pintype "passive"))
    )
    (net (code "109") (name "unconnected-(X1-R2_6-Pad2)") (class "Default")
      (node (ref "X1") (pin "2") (pinfunction "R2_6_2") (pintype "passive"))
    )
    (net (code "110") (name "unconnected-(X1-R2_7-Pad3)") (class "Default")
      (node (ref "X1") (pin "3") (pinfunction "R2_7_3") (pintype "passive"))
    )
    (net (code "111") (name "unconnected-(X2-R1_5-Pad4)") (class "Default")
      (node (ref "X2") (pin "4") (pinfunction "R1_5_4") (pintype "passive"))
    )
    (net (code "112") (name "unconnected-(X2-R1_6-Pad5)") (class "Default")
      (node (ref "X2") (pin "5") (pinfunction "R1_6_5") (pintype "passive"))
    )
    (net (code "113") (name "unconnected-(X2-R1_7-Pad6)") (class "Default")
      (node (ref "X2") (pin "6") (pinfunction "R1_7_6") (pintype "passive"))
    )
    (net (code "114") (name "unconnected-(X2-R2_5-Pad1)") (class "Default")
      (node (ref "X2") (pin "1") (pinfunction "R2_5_1") (pintype "passive"))
    )
    (net (code "115") (name "unconnected-(X2-R2_6-Pad2)") (class "Default")
      (node (ref "X2") (pin "2") (pinfunction "R2_6_2") (pintype "passive"))
    )
    (net (code "116") (name "unconnected-(X2-R2_7-Pad3)") (class "Default")
      (node (ref "X2") (pin "3") (pinfunction "R2_7_3") (pintype "passive"))
    )
    (net (code "117") (name "unconnected-(X3-R1_5-Pad4)") (class "Default")
      (node (ref "X3") (pin "4") (pinfunction "R1_5_4") (pintype "passive"))
    )
    (net (code "118") (name "unconnected-(X3-R1_6-Pad5)") (class "Default")
      (node (ref "X3") (pin "5") (pinfunction "R1_6_5") (pintype "passive"))
    )
    (net (code "119") (name "unconnected-(X3-R1_7-Pad6)") (class "Default")
      (node (ref "X3") (pin "6") (pinfunction "R1_7_6") (pintype "passive"))
    )
    (net (code "120") (name "unconnected-(X3-R2_5-Pad1)") (class "Default")
      (node (ref "X3") (pin "1") (pinfunction "R2_5_1") (pintype "passive"))
    )
    (net (code "121") (name "unconnected-(X3-R2_6-Pad2)") (class "Default")
      (node (ref "X3") (pin "2") (pinfunction "R2_6_2") (pintype "passive"))
    )
    (net (code "122") (name "unconnected-(X3-R2_7-Pad3)") (class "Default")
      (node (ref "X3") (pin "3") (pinfunction "R2_7_3") (pintype "passive"))
    )
    (net (code "123") (name "unconnected-(X4-R1_5-Pad4)") (class "Default")
      (node (ref "X4") (pin "4") (pinfunction "R1_5_4") (pintype "passive"))
    )
    (net (code "124") (name "unconnected-(X4-R1_6-Pad5)") (class "Default")
      (node (ref "X4") (pin "5") (pinfunction "R1_6_5") (pintype "passive"))
    )
    (net (code "125") (name "unconnected-(X4-R1_7-Pad6)") (class "Default")
      (node (ref "X4") (pin "6") (pinfunction "R1_7_6") (pintype "passive"))
    )
    (net (code "126") (name "unconnected-(X4-R2_5-Pad1)") (class "Default")
      (node (ref "X4") (pin "1") (pinfunction "R2_5_1") (pintype "passive"))
    )
    (net (code "127") (name "unconnected-(X4-R2_6-Pad2)") (class "Default")
      (node (ref "X4") (pin "2") (pinfunction "R2_6_2") (pintype "passive"))
    )
    (net (code "128") (name "unconnected-(X4-R2_7-Pad3)") (class "Default")
      (node (ref "X4") (pin "3") (pinfunction "R2_7_3") (pintype "passive"))
    )
    (net (code "129") (name "unconnected-(X5-R1_5-Pad4)") (class "Default")
      (node (ref "X5") (pin "4") (pinfunction "R1_5_4") (pintype "passive"))
    )
    (net (code "130") (name "unconnected-(X5-R1_6-Pad5)") (class "Default")
      (node (ref "X5") (pin "5") (pinfunction "R1_6_5") (pintype "passive"))
    )
    (net (code "131") (name "unconnected-(X5-R1_7-Pad6)") (class "Default")
      (node (ref "X5") (pin "6") (pinfunction "R1_7_6") (pintype "passive"))
    )
    (net (code "132") (name "unconnected-(X5-R2_5-Pad1)") (class "Default")
      (node (ref "X5") (pin "1") (pinfunction "R2_5_1") (pintype "passive"))
    )
    (net (code "133") (name "unconnected-(X5-R2_6-Pad2)") (class "Default")
      (node (ref "X5") (pin "2") (pinfunction "R2_6_2") (pintype "passive"))
    )
    (net (code "134") (name "unconnected-(X5-R2_7-Pad3)") (class "Default")
      (node (ref "X5") (pin "3") (pinfunction "R2_7_3") (pintype "passive"))
    )
    (net (code "135") (name "unconnected-(X6-R1_5-Pad4)") (class "Default")
      (node (ref "X6") (pin "4") (pinfunction "R1_5_4") (pintype "passive"))
    )
    (net (code "136") (name "unconnected-(X6-R1_6-Pad5)") (class "Default")
      (node (ref "X6") (pin "5") (pinfunction "R1_6_5") (pintype "passive"))
    )
    (net (code "137") (name "unconnected-(X6-R1_7-Pad6)") (class "Default")
      (node (ref "X6") (pin "6") (pinfunction "R1_7_6") (pintype "passive"))
    )
    (net (code "138") (name "unconnected-(X6-R2_5-Pad1)") (class "Default")
      (node (ref "X6") (pin "1") (pinfunction "R2_5_1") (pintype "passive"))
    )
    (net (code "139") (name "unconnected-(X6-R2_6-Pad2)") (class "Default")
      (node (ref "X6") (pin "2") (pinfunction "R2_6_2") (pintype "passive"))
    )
    (net (code "140") (name "unconnected-(X6-R2_7-Pad3)") (class "Default")
      (node (ref "X6") (pin "3") (pinfunction "R2_7_3") (pintype "passive"))
    )
    (net (code "141") (name "unconnected-(X7-R1_5-Pad4)") (class "Default")
      (node (ref "X7") (pin "4") (pinfunction "R1_5_4") (pintype "passive"))
    )
    (net (code "142") (name "unconnected-(X7-R1_6-Pad5)") (class "Default")
      (node (ref "X7") (pin "5") (pinfunction "R1_6_5") (pintype "passive"))
    )
    (net (code "143") (name "unconnected-(X7-R1_7-Pad6)") (class "Default")
      (node (ref "X7") (pin "6") (pinfunction "R1_7_6") (pintype "passive"))
    )
    (net (code "144") (name "unconnected-(X7-R2_5-Pad1)") (class "Default")
      (node (ref "X7") (pin "1") (pinfunction "R2_5_1") (pintype "passive"))
    )
    (net (code "145") (name "unconnected-(X7-R2_6-Pad2)") (class "Default")
      (node (ref "X7") (pin "2") (pinfunction "R2_6_2") (pintype "passive"))
    )
    (net (code "146") (name "unconnected-(X7-R2_7-Pad3)") (class "Default")
      (node (ref "X7") (pin "3") (pinfunction "R2_7_3") (pintype "passive"))
    )
    (net (code "147") (name "unconnected-(X8-R2_5-Pad1)") (class "Default")
      (node (ref "X8") (pin "1") (pinfunction "R2_5_1") (pintype "passive"))
    )
    (net (code "148") (name "unconnected-(X8-R2_6-Pad2)") (class "Default")
      (node (ref "X8") (pin "2") (pinfunction "R2_6_2") (pintype "passive"))
    )
    (net (code "149") (name "unconnected-(X8-R2_7-Pad3)") (class "Default")
      (node (ref "X8") (pin "3") (pinfunction "R2_7_3") (pintype "passive"))
    )
    (net (code "150") (name "unconnected-(X9-+V-Pad3)") (class "Default")
      (node (ref "X9") (pin "3") (pinfunction "+V_3") (pintype "passive"))
    )
    (net (code "151") (name "unconnected-(X9--V-Pad4)") (class "Default")
      (node (ref "X9") (pin "4") (pinfunction "-V_4") (pintype "passive"))
    )
  )
)
